# PC104.net
KiCad netlist of a schematic drawn in Altium Designer
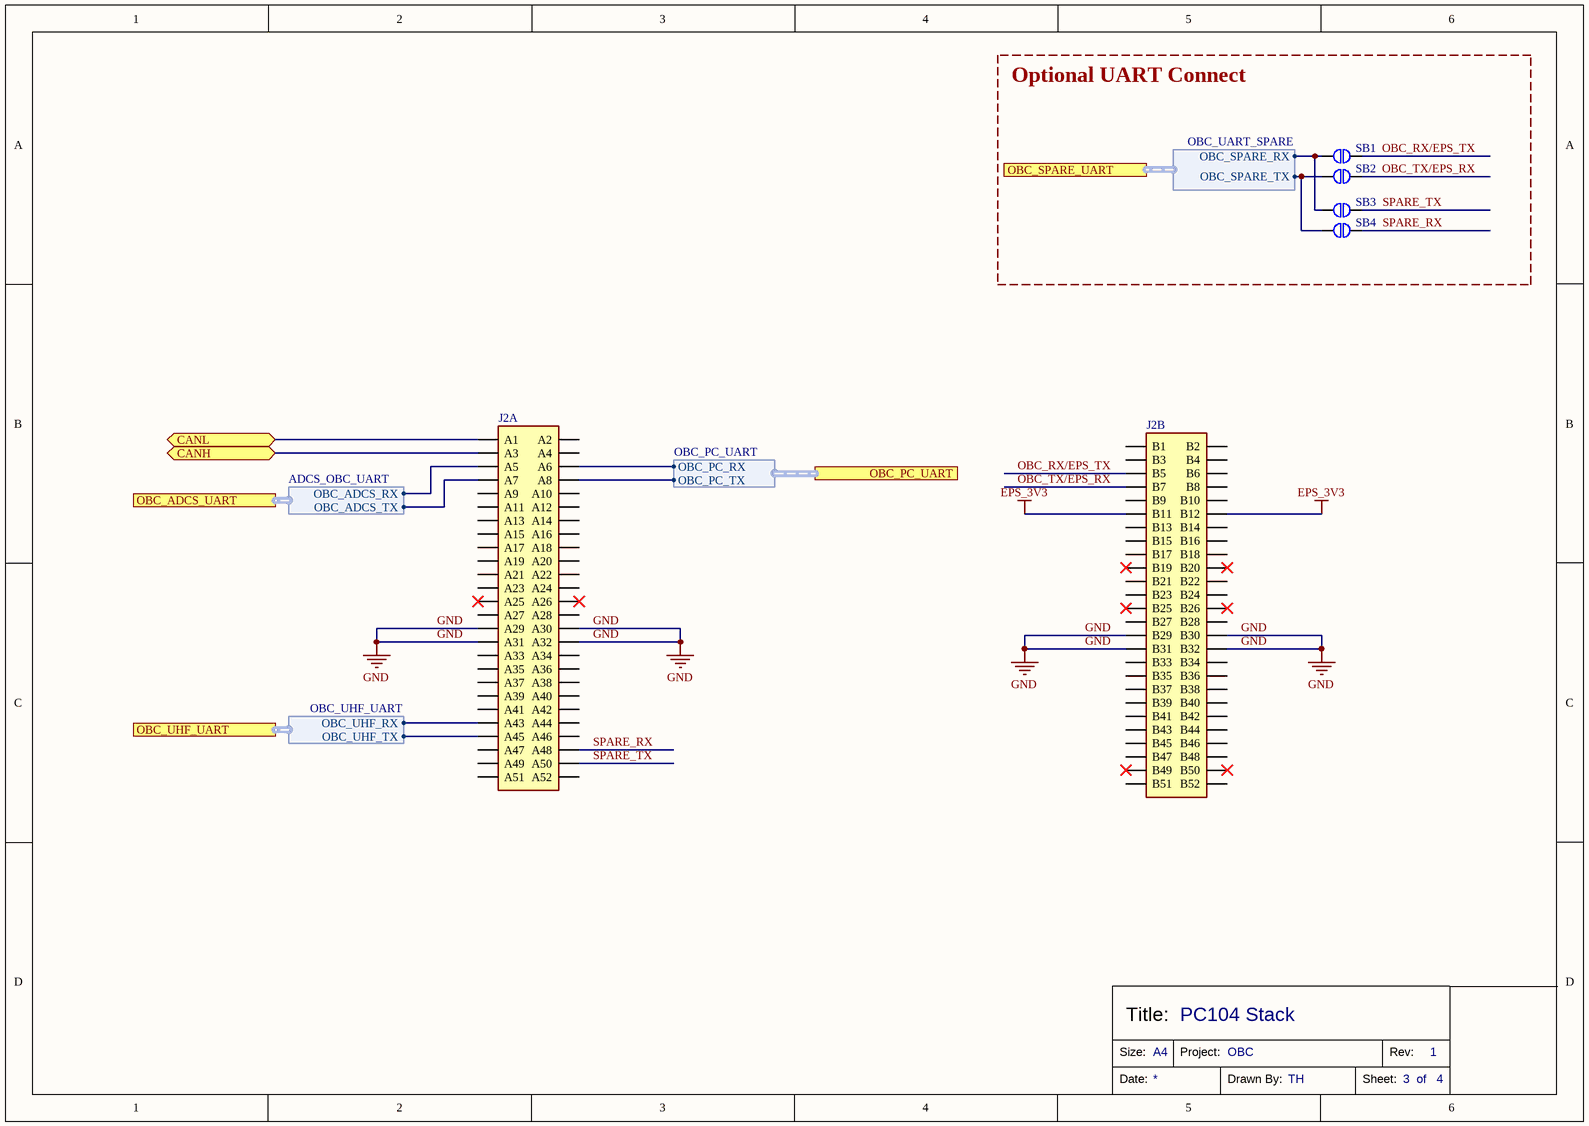
[diagram p0: PC104.SchDoc]

(export (version "E")
  (design (tool "Eeschema 10.0.6"))
  (components
    (comp (ref "J2")
      (value "SSQ-126-21-G-D")
      (footprint "PC104 STACK HEADER")
      (description "PC104 stack header, 2.54mm 4x26positions")
      (fields (field (name "DISTRIBUTOR PART NUMBER") "SSQ-126-21-G-D-ND"))
      (libsource (lib "Ahristi_Library") (part "PC104"))
    )
    (comp (ref "SB1")
      (value "Solder Bridge Jumper")
      (footprint "Solder Bridge")
      (libsource (lib "Ahristi_Library") (part "Solder Bridge Jumper"))
    )
    (comp (ref "SB2")
      (value "Solder Bridge Jumper")
      (footprint "Solder Bridge")
      (libsource (lib "Ahristi_Library") (part "Solder Bridge Jumper"))
    )
    (comp (ref "SB3")
      (value "Solder Bridge Jumper")
      (footprint "Solder Bridge")
      (libsource (lib "Ahristi_Library") (part "Solder Bridge Jumper"))
    )
    (comp (ref "SB4")
      (value "Solder Bridge Jumper")
      (footprint "Solder Bridge")
      (libsource (lib "Ahristi_Library") (part "Solder Bridge Jumper"))
    )
  )
  (nets
    (net (code "5") (name "/CANH") (class "Default")
      (node (ref "J2") (pin "A3") (pinfunction "A3_A3") (pintype "passive"))
    )
    (net (code "6") (name "/CANL") (class "Default")
      (node (ref "J2") (pin "A1") (pinfunction "A1_A1") (pintype "passive"))
    )
    (net (code "7") (name "/OBC_ADCS_RX") (class "Default")
      (node (ref "J2") (pin "A5") (pinfunction "A5_A5") (pintype "passive"))
    )
    (net (code "8") (name "/OBC_ADCS_TX") (class "Default")
      (node (ref "J2") (pin "A7") (pinfunction "A7_A7") (pintype "passive"))
    )
    (net (code "9") (name "/OBC_PC_RX") (class "Default")
      (node (ref "J2") (pin "A6") (pinfunction "A6_A6") (pintype "passive"))
    )
    (net (code "10") (name "/OBC_PC_TX") (class "Default")
      (node (ref "J2") (pin "A8") (pinfunction "A8_A8") (pintype "passive"))
    )
    (net (code "11") (name "/OBC_RX{slash}EPS_TX") (class "Default")
      (node (ref "J2") (pin "B5") (pinfunction "B5_B5") (pintype "passive"))
      (node (ref "SB1") (pin "1") (pinfunction "1_1") (pintype "passive"))
    )
    (net (code "12") (name "/OBC_SPARE_RX") (class "Default")
      (node (ref "SB1") (pin "2") (pinfunction "2_2") (pintype "passive"))
      (node (ref "SB3") (pin "2") (pinfunction "2_2") (pintype "passive"))
    )
    (net (code "13") (name "/OBC_SPARE_TX") (class "Default")
      (node (ref "SB2") (pin "2") (pinfunction "2_2") (pintype "passive"))
      (node (ref "SB4") (pin "2") (pinfunction "2_2") (pintype "passive"))
    )
    (net (code "14") (name "/OBC_TX{slash}EPS_RX") (class "Default")
      (node (ref "J2") (pin "B7") (pinfunction "B7_B7") (pintype "passive"))
      (node (ref "SB2") (pin "1") (pinfunction "1_1") (pintype "passive"))
    )
    (net (code "15") (name "/OBC_UHF_RX") (class "Default")
      (node (ref "J2") (pin "A43") (pinfunction "A43_A43") (pintype "passive"))
    )
    (net (code "16") (name "/OBC_UHF_TX") (class "Default")
      (node (ref "J2") (pin "A45") (pinfunction "A45_A45") (pintype "passive"))
    )
    (net (code "17") (name "/SPARE_RX") (class "Default")
      (node (ref "J2") (pin "A48") (pinfunction "A48_A48") (pintype "passive"))
      (node (ref "SB4") (pin "1") (pinfunction "1_1") (pintype "passive"))
    )
    (net (code "18") (name "/SPARE_TX") (class "Default")
      (node (ref "J2") (pin "A50") (pinfunction "A50_A50") (pintype "passive"))
      (node (ref "SB3") (pin "1") (pinfunction "1_1") (pintype "passive"))
    )
    (net (code "23") (name "EPS_3V3") (class "Default")
      (node (ref "J2") (pin "B11") (pinfunction "B11_B11") (pintype "passive"))
      (node (ref "J2") (pin "B12") (pinfunction "B12_B12") (pintype "passive"))
    )
    (net (code "24") (name "GND") (class "Default")
      (node (ref "J2") (pin "A29") (pinfunction "A29_A29") (pintype "passive"))
      (node (ref "J2") (pin "A30") (pinfunction "A30_A30") (pintype "passive"))
      (node (ref "J2") (pin "A31") (pinfunction "A31_A31") (pintype "passive"))
      (node (ref "J2") (pin "A32") (pinfunction "A32_A32") (pintype "passive"))
      (node (ref "J2") (pin "B29") (pinfunction "B29_B29") (pintype "passive"))
      (node (ref "J2") (pin "B30") (pinfunction "B30_B30") (pintype "passive"))
      (node (ref "J2") (pin "B31") (pinfunction "B31_B31") (pintype "passive"))
      (node (ref "J2") (pin "B32") (pinfunction "B32_B32") (pintype "passive"))
    )
    (net (code "25") (name "unconnected-(J2-PadA2)") (class "Default")
      (node (ref "J2") (pin "A2") (pinfunction "A2_A2") (pintype "passive"))
    )
    (net (code "26") (name "unconnected-(J2-PadA4)") (class "Default")
      (node (ref "J2") (pin "A4") (pinfunction "A4_A4") (pintype "passive"))
    )
    (net (code "27") (name "unconnected-(J2-PadA9)") (class "Default")
      (node (ref "J2") (pin "A9") (pinfunction "A9_A9") (pintype "passive"))
    )
    (net (code "28") (name "unconnected-(J2-PadA10)") (class "Default")
      (node (ref "J2") (pin "A10") (pinfunction "A10_A10") (pintype "passive"))
    )
    (net (code "29") (name "unconnected-(J2-PadA11)") (class "Default")
      (node (ref "J2") (pin "A11") (pinfunction "A11_A11") (pintype "passive"))
    )
    (net (code "30") (name "unconnected-(J2-PadA12)") (class "Default")
      (node (ref "J2") (pin "A12") (pinfunction "A12_A12") (pintype "passive"))
    )
    (net (code "31") (name "unconnected-(J2-PadA13)") (class "Default")
      (node (ref "J2") (pin "A13") (pinfunction "A13_A13") (pintype "passive"))
    )
    (net (code "32") (name "unconnected-(J2-PadA14)") (class "Default")
      (node (ref "J2") (pin "A14") (pinfunction "A14_A14") (pintype "passive"))
    )
    (net (code "33") (name "unconnected-(J2-PadA15)") (class "Default")
      (node (ref "J2") (pin "A15") (pinfunction "A15_A15") (pintype "passive"))
    )
    (net (code "34") (name "unconnected-(J2-PadA16)") (class "Default")
      (node (ref "J2") (pin "A16") (pinfunction "A16_A16") (pintype "passive"))
    )
    (net (code "35") (name "unconnected-(J2-PadA17)") (class "Default")
      (node (ref "J2") (pin "A17") (pinfunction "A17_A17") (pintype "passive"))
    )
    (net (code "36") (name "unconnected-(J2-PadA18)") (class "Default")
      (node (ref "J2") (pin "A18") (pinfunction "A18_A18") (pintype "passive"))
    )
    (net (code "37") (name "unconnected-(J2-PadA19)") (class "Default")
      (node (ref "J2") (pin "A19") (pinfunction "A19_A19") (pintype "passive"))
    )
    (net (code "38") (name "unconnected-(J2-PadA20)") (class "Default")
      (node (ref "J2") (pin "A20") (pinfunction "A20_A20") (pintype "passive"))
    )
    (net (code "39") (name "unconnected-(J2-PadA21)") (class "Default")
      (node (ref "J2") (pin "A21") (pinfunction "A21_A21") (pintype "passive"))
    )
    (net (code "40") (name "unconnected-(J2-PadA22)") (class "Default")
      (node (ref "J2") (pin "A22") (pinfunction "A22_A22") (pintype "passive"))
    )
    (net (code "41") (name "unconnected-(J2-PadA23)") (class "Default")
      (node (ref "J2") (pin "A23") (pinfunction "A23_A23") (pintype "passive"))
    )
    (net (code "42") (name "unconnected-(J2-PadA24)") (class "Default")
      (node (ref "J2") (pin "A24") (pinfunction "A24_A24") (pintype "passive"))
    )
    (net (code "43") (name "unconnected-(J2-PadA25)") (class "Default")
      (node (ref "J2") (pin "A25") (pinfunction "A25_A25") (pintype "passive+no_connect"))
    )
    (net (code "44") (name "unconnected-(J2-PadA26)") (class "Default")
      (node (ref "J2") (pin "A26") (pinfunction "A26_A26") (pintype "passive+no_connect"))
    )
    (net (code "45") (name "unconnected-(J2-PadA27)") (class "Default")
      (node (ref "J2") (pin "A27") (pinfunction "A27_A27") (pintype "passive"))
    )
    (net (code "46") (name "unconnected-(J2-PadA28)") (class "Default")
      (node (ref "J2") (pin "A28") (pinfunction "A28_A28") (pintype "passive"))
    )
    (net (code "47") (name "unconnected-(J2-PadA33)") (class "Default")
      (node (ref "J2") (pin "A33") (pinfunction "A33_A33") (pintype "passive"))
    )
    (net (code "48") (name "unconnected-(J2-PadA34)") (class "Default")
      (node (ref "J2") (pin "A34") (pinfunction "A34_A34") (pintype "passive"))
    )
    (net (code "49") (name "unconnected-(J2-PadA35)") (class "Default")
      (node (ref "J2") (pin "A35") (pinfunction "A35_A35") (pintype "passive"))
    )
    (net (code "50") (name "unconnected-(J2-PadA36)") (class "Default")
      (node (ref "J2") (pin "A36") (pinfunction "A36_A36") (pintype "passive"))
    )
    (net (code "51") (name "unconnected-(J2-PadA37)") (class "Default")
      (node (ref "J2") (pin "A37") (pinfunction "A37_A37") (pintype "passive"))
    )
    (net (code "52") (name "unconnected-(J2-PadA38)") (class "Default")
      (node (ref "J2") (pin "A38") (pinfunction "A38_A38") (pintype "passive"))
    )
    (net (code "53") (name "unconnected-(J2-PadA39)") (class "Default")
      (node (ref "J2") (pin "A39") (pinfunction "A39_A39") (pintype "passive"))
    )
    (net (code "54") (name "unconnected-(J2-PadA40)") (class "Default")
      (node (ref "J2") (pin "A40") (pinfunction "A40_A40") (pintype "passive"))
    )
    (net (code "55") (name "unconnected-(J2-PadA41)") (class "Default")
      (node (ref "J2") (pin "A41") (pinfunction "A41_A41") (pintype "passive"))
    )
    (net (code "56") (name "unconnected-(J2-PadA42)") (class "Default")
      (node (ref "J2") (pin "A42") (pinfunction "A42_A42") (pintype "passive"))
    )
    (net (code "57") (name "unconnected-(J2-PadA44)") (class "Default")
      (node (ref "J2") (pin "A44") (pinfunction "A44_A44") (pintype "passive"))
    )
    (net (code "58") (name "unconnected-(J2-PadA46)") (class "Default")
      (node (ref "J2") (pin "A46") (pinfunction "A46_A46") (pintype "passive"))
    )
    (net (code "59") (name "unconnected-(J2-PadA47)") (class "Default")
      (node (ref "J2") (pin "A47") (pinfunction "A47_A47") (pintype "passive"))
    )
    (net (code "60") (name "unconnected-(J2-PadA49)") (class "Default")
      (node (ref "J2") (pin "A49") (pinfunction "A49_A49") (pintype "passive"))
    )
    (net (code "61") (name "unconnected-(J2-PadA51)") (class "Default")
      (node (ref "J2") (pin "A51") (pinfunction "A51_A51") (pintype "passive"))
    )
    (net (code "62") (name "unconnected-(J2-PadA52)") (class "Default")
      (node (ref "J2") (pin "A52") (pinfunction "A52_A52") (pintype "passive"))
    )
    (net (code "63") (name "unconnected-(J2-PadB1)") (class "Default")
      (node (ref "J2") (pin "B1") (pinfunction "B1_B1") (pintype "passive"))
    )
    (net (code "64") (name "unconnected-(J2-PadB2)") (class "Default")
      (node (ref "J2") (pin "B2") (pinfunction "B2_B2") (pintype "passive"))
    )
    (net (code "65") (name "unconnected-(J2-PadB3)") (class "Default")
      (node (ref "J2") (pin "B3") (pinfunction "B3_B3") (pintype "passive"))
    )
    (net (code "66") (name "unconnected-(J2-PadB4)") (class "Default")
      (node (ref "J2") (pin "B4") (pinfunction "B4_B4") (pintype "passive"))
    )
    (net (code "67") (name "unconnected-(J2-PadB6)") (class "Default")
      (node (ref "J2") (pin "B6") (pinfunction "B6_B6") (pintype "passive"))
    )
    (net (code "68") (name "unconnected-(J2-PadB8)") (class "Default")
      (node (ref "J2") (pin "B8") (pinfunction "B8_B8") (pintype "passive"))
    )
    (net (code "69") (name "unconnected-(J2-PadB9)") (class "Default")
      (node (ref "J2") (pin "B9") (pinfunction "B9_B9") (pintype "passive"))
    )
    (net (code "70") (name "unconnected-(J2-PadB10)") (class "Default")
      (node (ref "J2") (pin "B10") (pinfunction "B10_B10") (pintype "passive"))
    )
    (net (code "71") (name "unconnected-(J2-PadB13)") (class "Default")
      (node (ref "J2") (pin "B13") (pinfunction "B13_B13") (pintype "passive"))
    )
    (net (code "72") (name "unconnected-(J2-PadB14)") (class "Default")
      (node (ref "J2") (pin "B14") (pinfunction "B14_B14") (pintype "passive"))
    )
    (net (code "73") (name "unconnected-(J2-PadB15)") (class "Default")
      (node (ref "J2") (pin "B15") (pinfunction "B15_B15") (pintype "passive"))
    )
    (net (code "74") (name "unconnected-(J2-PadB16)") (class "Default")
      (node (ref "J2") (pin "B16") (pinfunction "B16_B16") (pintype "passive"))
    )
    (net (code "75") (name "unconnected-(J2-PadB17)") (class "Default")
      (node (ref "J2") (pin "B17") (pinfunction "B17_B17") (pintype "passive"))
    )
    (net (code "76") (name "unconnected-(J2-PadB18)") (class "Default")
      (node (ref "J2") (pin "B18") (pinfunction "B18_B18") (pintype "passive"))
    )
    (net (code "77") (name "unconnected-(J2-PadB19)") (class "Default")
      (node (ref "J2") (pin "B19") (pinfunction "B19_B19") (pintype "passive+no_connect"))
    )
    (net (code "78") (name "unconnected-(J2-PadB20)") (class "Default")
      (node (ref "J2") (pin "B20") (pinfunction "B20_B20") (pintype "passive+no_connect"))
    )
    (net (code "79") (name "unconnected-(J2-PadB21)") (class "Default")
      (node (ref "J2") (pin "B21") (pinfunction "B21_B21") (pintype "passive"))
    )
    (net (code "80") (name "unconnected-(J2-PadB22)") (class "Default")
      (node (ref "J2") (pin "B22") (pinfunction "B22_B22") (pintype "passive"))
    )
    (net (code "81") (name "unconnected-(J2-PadB23)") (class "Default")
      (node (ref "J2") (pin "B23") (pinfunction "B23_B23") (pintype "passive"))
    )
    (net (code "82") (name "unconnected-(J2-PadB24)") (class "Default")
      (node (ref "J2") (pin "B24") (pinfunction "B24_B24") (pintype "passive"))
    )
    (net (code "83") (name "unconnected-(J2-PadB25)") (class "Default")
      (node (ref "J2") (pin "B25") (pinfunction "B25_B25") (pintype "passive+no_connect"))
    )
    (net (code "84") (name "unconnected-(J2-PadB26)") (class "Default")
      (node (ref "J2") (pin "B26") (pinfunction "B26_B26") (pintype "passive+no_connect"))
    )
    (net (code "85") (name "unconnected-(J2-PadB27)") (class "Default")
      (node (ref "J2") (pin "B27") (pinfunction "B27_B27") (pintype "passive"))
    )
    (net (code "86") (name "unconnected-(J2-PadB28)") (class "Default")
      (node (ref "J2") (pin "B28") (pinfunction "B28_B28") (pintype "passive"))
    )
    (net (code "87") (name "unconnected-(J2-PadB33)") (class "Default")
      (node (ref "J2") (pin "B33") (pinfunction "B33_B33") (pintype "passive"))
    )
    (net (code "88") (name "unconnected-(J2-PadB34)") (class "Default")
      (node (ref "J2") (pin "B34") (pinfunction "B34_B34") (pintype "passive"))
    )
    (net (code "89") (name "unconnected-(J2-PadB35)") (class "Default")
      (node (ref "J2") (pin "B35") (pinfunction "B35_B35") (pintype "passive"))
    )
    (net (code "90") (name "unconnected-(J2-PadB36)") (class "Default")
      (node (ref "J2") (pin "B36") (pinfunction "B36_B36") (pintype "passive"))
    )
    (net (code "91") (name "unconnected-(J2-PadB37)") (class "Default")
      (node (ref "J2") (pin "B37") (pinfunction "B37_B37") (pintype "passive"))
    )
    (net (code "92") (name "unconnected-(J2-PadB38)") (class "Default")
      (node (ref "J2") (pin "B38") (pinfunction "B38_B38") (pintype "passive"))
    )
    (net (code "93") (name "unconnected-(J2-PadB39)") (class "Default")
      (node (ref "J2") (pin "B39") (pinfunction "B39_B39") (pintype "passive"))
    )
    (net (code "94") (name "unconnected-(J2-PadB40)") (class "Default")
      (node (ref "J2") (pin "B40") (pinfunction "B40_B40") (pintype "passive"))
    )
    (net (code "95") (name "unconnected-(J2-PadB41)") (class "Default")
      (node (ref "J2") (pin "B41") (pinfunction "B41_B41") (pintype "passive"))
    )
    (net (code "96") (name "unconnected-(J2-PadB42)") (class "Default")
      (node (ref "J2") (pin "B42") (pinfunction "B42_B42") (pintype "passive"))
    )
    (net (code "97") (name "unconnected-(J2-PadB43)") (class "Default")
      (node (ref "J2") (pin "B43") (pinfunction "B43_B43") (pintype "passive"))
    )
    (net (code "98") (name "unconnected-(J2-PadB44)") (class "Default")
      (node (ref "J2") (pin "B44") (pinfunction "B44_B44") (pintype "passive"))
    )
    (net (code "99") (name "unconnected-(J2-PadB45)") (class "Default")
      (node (ref "J2") (pin "B45") (pinfunction "B45_B45") (pintype "passive"))
    )
    (net (code "100") (name "unconnected-(J2-PadB46)") (class "Default")
      (node (ref "J2") (pin "B46") (pinfunction "B46_B46") (pintype "passive"))
    )
    (net (code "101") (name "unconnected-(J2-PadB47)") (class "Default")
      (node (ref "J2") (pin "B47") (pinfunction "B47_B47") (pintype "passive"))
    )
    (net (code "102") (name "unconnected-(J2-PadB48)") (class "Default")
      (node (ref "J2") (pin "B48") (pinfunction "B48_B48") (pintype "passive"))
    )
    (net (code "103") (name "unconnected-(J2-PadB49)") (class "Default")
      (node (ref "J2") (pin "B49") (pinfunction "B49_B49") (pintype "passive+no_connect"))
    )
    (net (code "104") (name "unconnected-(J2-PadB50)") (class "Default")
      (node (ref "J2") (pin "B50") (pinfunction "B50_B50") (pintype "passive+no_connect"))
    )
    (net (code "105") (name "unconnected-(J2-PadB51)") (class "Default")
      (node (ref "J2") (pin "B51") (pinfunction "B51_B51") (pintype "passive"))
    )
    (net (code "106") (name "unconnected-(J2-PadB52)") (class "Default")
      (node (ref "J2") (pin "B52") (pinfunction "B52_B52") (pintype "passive"))
    )
  )
)
